# Apo_Board_2017_PB.net
KiCad netlist of a schematic drawn in EAGLE
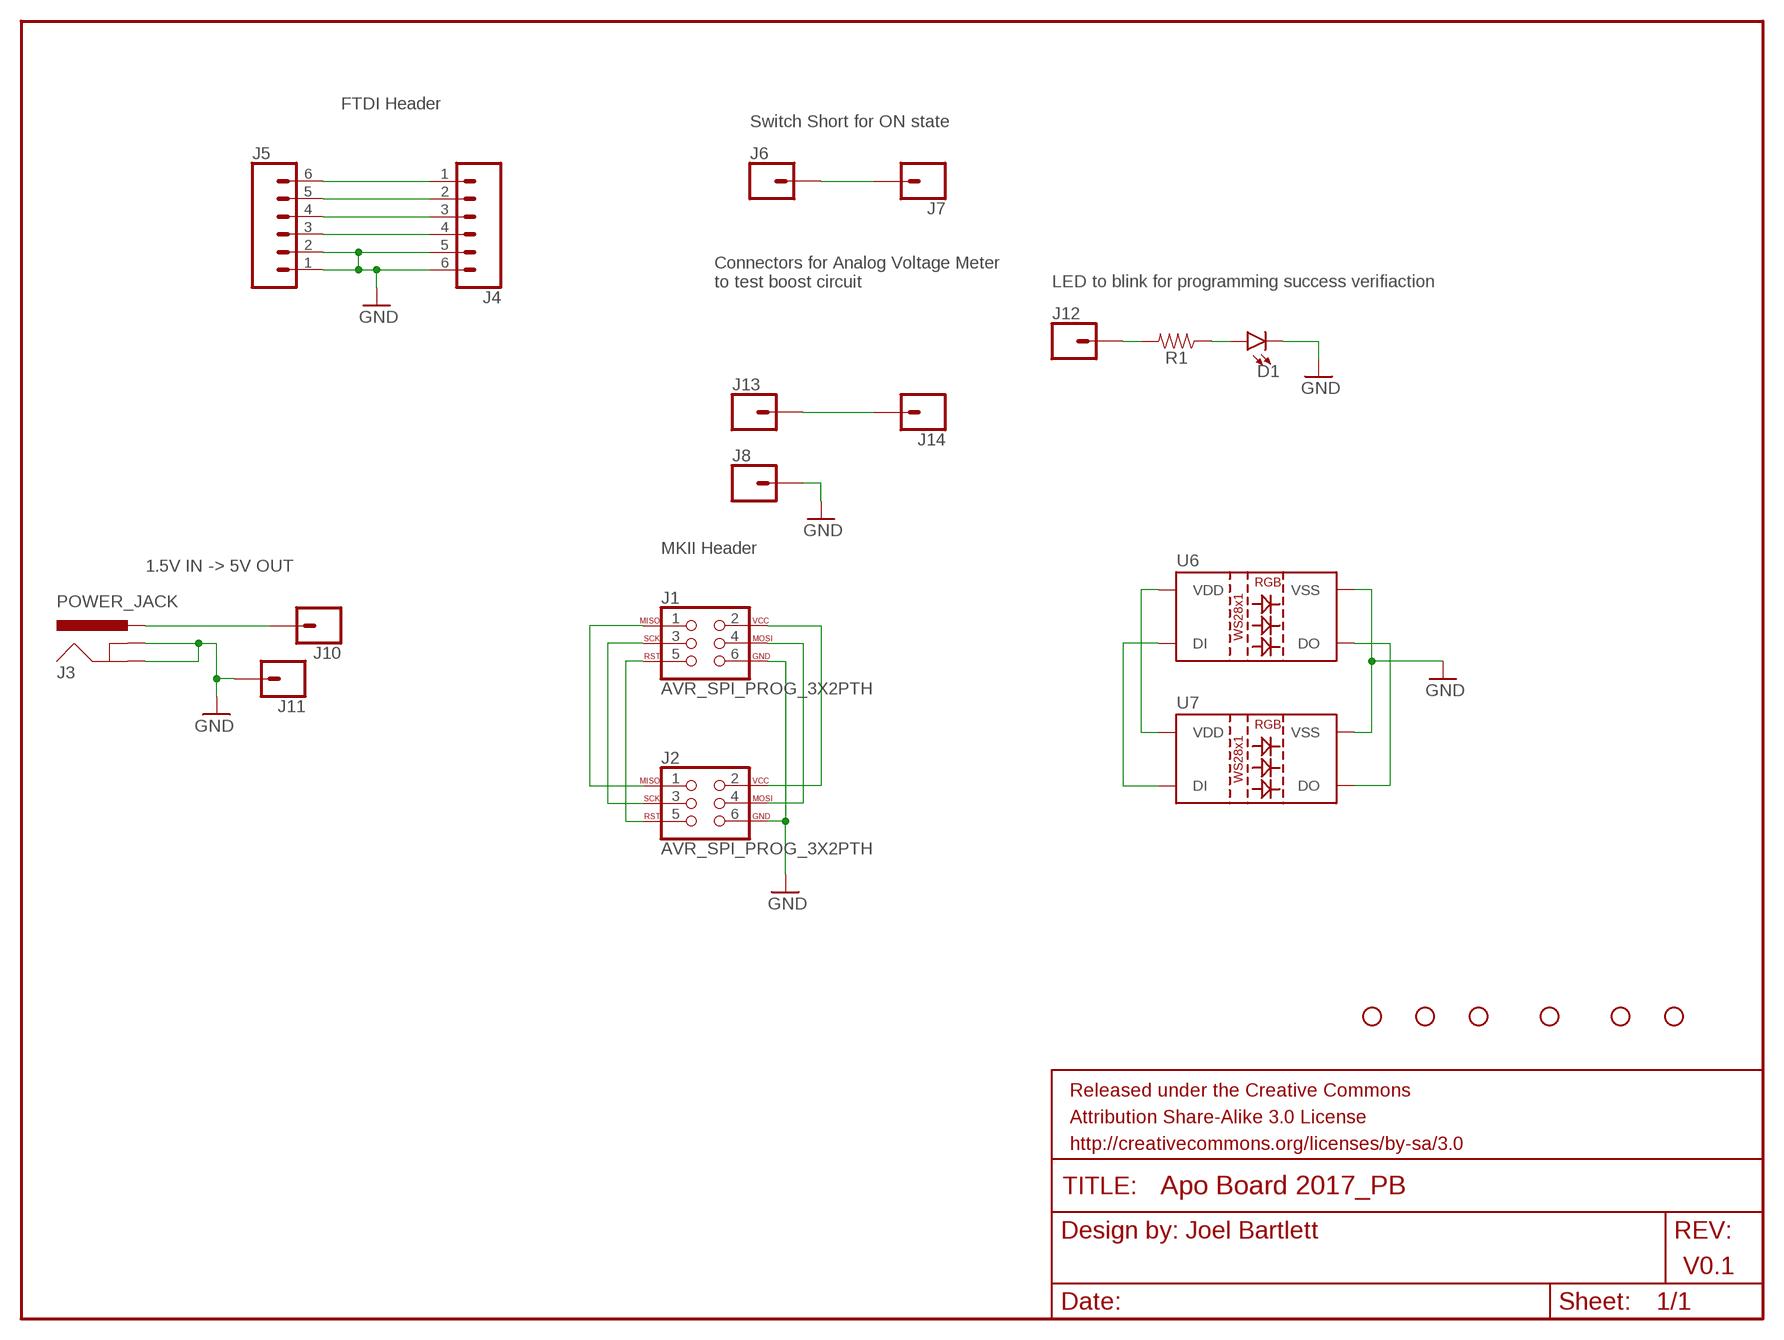
[diagram p0: schematic, sheet 1]

(export (version "E")
  (design (tool "Eeschema 10.0.6"))
  (components
    (comp (ref "D1")
      (value "LED5MM")
      (footprint "eagle-import:LED_5MM")
      (libsource (lib "eagle-import") (part "LED5MM"))
    )
    (comp (ref "FRAME1")
      (value "FRAME-LETTER")
      (footprint "eagle-import:CREATIVE_COMMONS")
      (libsource (lib "eagle-import") (part "FRAME-LETTER"))
    )
    (comp (ref "H1")
      (value "STAND-OFF")
      (footprint "eagle-import:STAND-OFF")
      (libsource (lib "eagle-import") (part "STAND-OFF"))
    )
    (comp (ref "H2")
      (value "STAND-OFF")
      (footprint "eagle-import:STAND-OFF")
      (libsource (lib "eagle-import") (part "STAND-OFF"))
    )
    (comp (ref "H3")
      (value "STAND-OFF")
      (footprint "eagle-import:STAND-OFF")
      (libsource (lib "eagle-import") (part "STAND-OFF"))
    )
    (comp (ref "H4")
      (value "STAND-OFF")
      (footprint "eagle-import:STAND-OFF")
      (libsource (lib "eagle-import") (part "STAND-OFF"))
    )
    (comp (ref "H5")
      (value "STAND-OFF")
      (footprint "eagle-import:STAND-OFF")
      (libsource (lib "eagle-import") (part "STAND-OFF"))
    )
    (comp (ref "H6")
      (value "STAND-OFF")
      (footprint "eagle-import:STAND-OFF")
      (libsource (lib "eagle-import") (part "STAND-OFF"))
    )
    (comp (ref "J1")
      (value "AVR_SPI_PROG_3X2PTH")
      (footprint "eagle-import:2X3")
      (libsource (lib "eagle-import") (part "AVR_SPI_PROG_3X2PTH"))
    )
    (comp (ref "J2")
      (value "AVR_SPI_PROG_3X2PTH")
      (footprint "eagle-import:2X3")
      (libsource (lib "eagle-import") (part "AVR_SPI_PROG_3X2PTH"))
    )
    (comp (ref "J3")
      (value "POWER_JACK")
      (footprint "eagle-import:POWER_JACK_PTH")
      (libsource (lib "eagle-import") (part "POWER_JACK"))
    )
    (comp (ref "J4")
      (value "CONN_06LONGPADS")
      (footprint "eagle-import:1X06_LONGPADS")
      (libsource (lib "eagle-import") (part "CONN_06LONGPADS"))
    )
    (comp (ref "J5")
      (value "CONN_06LONGPADS")
      (footprint "eagle-import:1X06_LONGPADS")
      (libsource (lib "eagle-import") (part "CONN_06LONGPADS"))
    )
    (comp (ref "J6")
      (value "CONN_01PTH_LONGPAD")
      (footprint "eagle-import:1X01_LONGPAD")
      (libsource (lib "eagle-import") (part "CONN_01PTH_LONGPAD"))
    )
    (comp (ref "J7")
      (value "CONN_01PTH_LONGPAD")
      (footprint "eagle-import:1X01_LONGPAD")
      (libsource (lib "eagle-import") (part "CONN_01PTH_LONGPAD"))
    )
    (comp (ref "J8")
      (value "CONN_01PTH_LONGPAD")
      (footprint "eagle-import:1X01_LONGPAD")
      (libsource (lib "eagle-import") (part "CONN_01PTH_LONGPAD"))
    )
    (comp (ref "J10")
      (value "CONN_01PTH_LONGPAD")
      (footprint "eagle-import:1X01_LONGPAD")
      (libsource (lib "eagle-import") (part "CONN_01PTH_LONGPAD"))
    )
    (comp (ref "J11")
      (value "CONN_01PTH_LONGPAD")
      (footprint "eagle-import:1X01_LONGPAD")
      (libsource (lib "eagle-import") (part "CONN_01PTH_LONGPAD"))
    )
    (comp (ref "J12")
      (value "CONN_01PTH_LONGPAD")
      (footprint "eagle-import:1X01_LONGPAD")
      (libsource (lib "eagle-import") (part "CONN_01PTH_LONGPAD"))
    )
    (comp (ref "J13")
      (value "CONN_01PTH_LONGPAD")
      (footprint "eagle-import:1X01_LONGPAD")
      (libsource (lib "eagle-import") (part "CONN_01PTH_LONGPAD"))
    )
    (comp (ref "J14")
      (value "CONN_01PTH_LONGPAD")
      (footprint "eagle-import:1X01_LONGPAD")
      (libsource (lib "eagle-import") (part "CONN_01PTH_LONGPAD"))
    )
    (comp (ref "R1")
      (value "RESISTORAXIAL-0.3-KIT")
      (footprint "eagle-import:AXIAL-0.3-KIT")
      (libsource (lib "eagle-import") (part "RESISTORAXIAL-0.3-KIT"))
    )
    (comp (ref "U6")
      (value "LED-TRICOLOR-5050-ICWS2812-THRU-KIT")
      (footprint "eagle-import:LED-RGB-THRU-KIT")
      (libsource (lib "eagle-import") (part "LED-TRICOLOR-5050-ICWS2812-THRU-KIT"))
    )
    (comp (ref "U7")
      (value "LED-TRICOLOR-5050-ICWS2812-THRU-KIT")
      (footprint "eagle-import:LED-RGB-THRU-KIT")
      (libsource (lib "eagle-import") (part "LED-TRICOLOR-5050-ICWS2812-THRU-KIT"))
    )
  )
  (nets
    (net (code "1") (name "GND") (class "Default")
      (node (ref "D1") (pin "K") (pinfunction "C_K") (pintype "passive"))
      (node (ref "J1") (pin "6") (pinfunction "6_6") (pintype "passive"))
      (node (ref "J11") (pin "1") (pinfunction "1_1") (pintype "passive"))
      (node (ref "J2") (pin "6") (pinfunction "6_6") (pintype "passive"))
      (node (ref "J3") (pin "GND") (pinfunction "GND_GND") (pintype "bidirectional"))
      (node (ref "J3") (pin "GNDBREAK") (pinfunction "GNDBREAK_GNDBREAK") (pintype "bidirectional"))
      (node (ref "J4") (pin "5") (pinfunction "5_5") (pintype "passive"))
      (node (ref "J4") (pin "6") (pinfunction "6_6") (pintype "passive"))
      (node (ref "J5") (pin "1") (pinfunction "1_1") (pintype "passive"))
      (node (ref "J5") (pin "2") (pinfunction "2_2") (pintype "passive"))
      (node (ref "J8") (pin "1") (pinfunction "1_1") (pintype "passive"))
      (node (ref "U6") (pin "3") (pinfunction "VSS_3") (pintype "bidirectional"))
      (node (ref "U7") (pin "3") (pinfunction "VSS_3") (pintype "bidirectional"))
    )
    (net (code "2") (name "Net-(J1-Pad1)") (class "Default")
      (node (ref "J1") (pin "1") (pinfunction "1_1") (pintype "passive"))
      (node (ref "J2") (pin "1") (pinfunction "1_1") (pintype "passive"))
    )
    (net (code "3") (name "Net-(J1-Pad2)") (class "Default")
      (node (ref "J1") (pin "2") (pinfunction "2_2") (pintype "passive"))
      (node (ref "J2") (pin "2") (pinfunction "2_2") (pintype "passive"))
    )
    (net (code "4") (name "Net-(J1-Pad3)") (class "Default")
      (node (ref "J1") (pin "3") (pinfunction "3_3") (pintype "passive"))
      (node (ref "J2") (pin "3") (pinfunction "3_3") (pintype "passive"))
    )
    (net (code "5") (name "Net-(J1-Pad4)") (class "Default")
      (node (ref "J1") (pin "4") (pinfunction "4_4") (pintype "passive"))
      (node (ref "J2") (pin "4") (pinfunction "4_4") (pintype "passive"))
    )
    (net (code "6") (name "Net-(J1-Pad5)") (class "Default")
      (node (ref "J1") (pin "5") (pinfunction "5_5") (pintype "passive"))
      (node (ref "J2") (pin "5") (pinfunction "5_5") (pintype "passive"))
    )
    (net (code "7") (name "Net-(J4-Pad1)") (class "Default")
      (node (ref "J4") (pin "1") (pinfunction "1_1") (pintype "passive"))
      (node (ref "J5") (pin "6") (pinfunction "6_6") (pintype "passive"))
    )
    (net (code "8") (name "Net-(J4-Pad2)") (class "Default")
      (node (ref "J4") (pin "2") (pinfunction "2_2") (pintype "passive"))
      (node (ref "J5") (pin "5") (pinfunction "5_5") (pintype "passive"))
    )
    (net (code "9") (name "Net-(J4-Pad3)") (class "Default")
      (node (ref "J4") (pin "3") (pinfunction "3_3") (pintype "passive"))
      (node (ref "J5") (pin "4") (pinfunction "4_4") (pintype "passive"))
    )
    (net (code "10") (name "Net-(J4-Pad4)") (class "Default")
      (node (ref "J4") (pin "4") (pinfunction "4_4") (pintype "passive"))
      (node (ref "J5") (pin "3") (pinfunction "3_3") (pintype "passive"))
    )
    (net (code "11") (name "Net-(J6-Pad1)") (class "Default")
      (node (ref "J6") (pin "1") (pinfunction "1_1") (pintype "passive"))
      (node (ref "J7") (pin "1") (pinfunction "1_1") (pintype "passive"))
    )
    (net (code "12") (name "Net-(J10-Pad1)") (class "Default")
      (node (ref "J10") (pin "1") (pinfunction "1_1") (pintype "passive"))
      (node (ref "J3") (pin "PWR") (pinfunction "PWR_PWR") (pintype "bidirectional"))
    )
    (net (code "13") (name "Net-(J13-Pad1)") (class "Default")
      (node (ref "J13") (pin "1") (pinfunction "1_1") (pintype "passive"))
      (node (ref "J14") (pin "1") (pinfunction "1_1") (pintype "passive"))
    )
    (net (code "14") (name "Net-(R1-1)") (class "Default")
      (node (ref "D1") (pin "A") (pinfunction "A_A") (pintype "passive"))
      (node (ref "R1") (pin "P$1") (pinfunction "1_P$1") (pintype "passive"))
    )
    (net (code "15") (name "Net-(R1-2)") (class "Default")
      (node (ref "J12") (pin "1") (pinfunction "1_1") (pintype "passive"))
      (node (ref "R1") (pin "P$2") (pinfunction "2_P$2") (pintype "passive"))
    )
    (net (code "16") (name "Net-(U6-DI)") (class "Default")
      (node (ref "U6") (pin "1") (pinfunction "DI_1") (pintype "bidirectional"))
      (node (ref "U7") (pin "1") (pinfunction "DI_1") (pintype "bidirectional"))
    )
    (net (code "17") (name "Net-(U6-DO)") (class "Default")
      (node (ref "U6") (pin "4") (pinfunction "DO_4") (pintype "bidirectional"))
      (node (ref "U7") (pin "4") (pinfunction "DO_4") (pintype "bidirectional"))
    )
    (net (code "18") (name "Net-(U6-VDD)") (class "Default")
      (node (ref "U6") (pin "2") (pinfunction "VDD_2") (pintype "bidirectional"))
      (node (ref "U7") (pin "2") (pinfunction "VDD_2") (pintype "bidirectional"))
    )
  )
)
